# Sheet1.net
KiCad netlist of a schematic drawn in Altium Designer
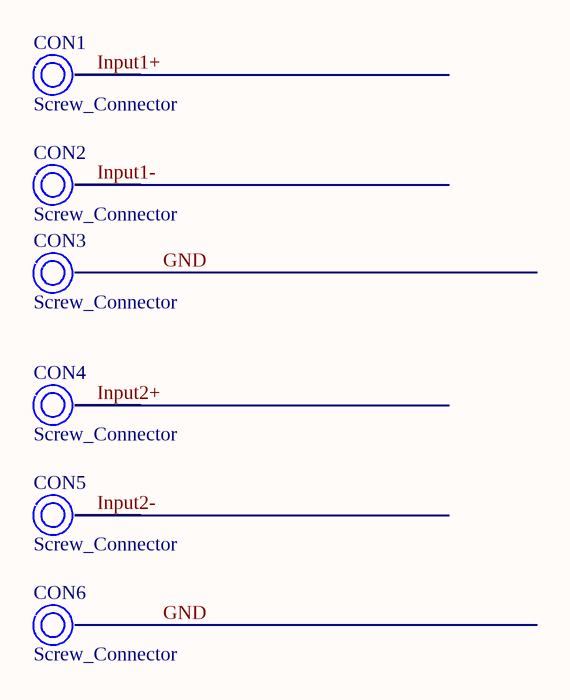
[diagram p0: Sheet1.SchDoc]

(export (version "E")
  (design (tool "Eeschema 10.0.6"))
  (components
    (comp (ref "CON1")
      (value "Screw_Connector")
      (footprint "Screw6x6")
      (libsource (lib "PCB_Project") (part "Screw_Connector"))
    )
    (comp (ref "CON2")
      (value "Screw_Connector")
      (footprint "Screw6x6")
      (libsource (lib "PCB_Project") (part "Screw_Connector"))
    )
    (comp (ref "CON3")
      (value "Screw_Connector")
      (footprint "Screw6x6")
      (libsource (lib "PCB_Project") (part "Screw_Connector"))
    )
    (comp (ref "CON4")
      (value "Screw_Connector")
      (footprint "Screw6x6")
      (libsource (lib "PCB_Project") (part "Screw_Connector"))
    )
    (comp (ref "CON5")
      (value "Screw_Connector")
      (footprint "Screw6x6")
      (libsource (lib "PCB_Project") (part "Screw_Connector"))
    )
    (comp (ref "CON6")
      (value "Screw_Connector")
      (footprint "Screw6x6")
      (libsource (lib "PCB_Project") (part "Screw_Connector"))
    )
  )
  (nets
    (net (code "1") (name "/GND") (class "Default")
      (node (ref "CON3") (pin "1") (pinfunction "1_1") (pintype "passive"))
      (node (ref "CON6") (pin "1") (pinfunction "1_1") (pintype "passive"))
    )
    (net (code "2") (name "/Input1+") (class "Default")
      (node (ref "CON1") (pin "1") (pinfunction "1_1") (pintype "passive"))
    )
    (net (code "3") (name "/Input1-") (class "Default")
      (node (ref "CON2") (pin "1") (pinfunction "1_1") (pintype "passive"))
    )
    (net (code "4") (name "/Input2+") (class "Default")
      (node (ref "CON4") (pin "1") (pinfunction "1_1") (pintype "passive"))
    )
    (net (code "5") (name "/Input2-") (class "Default")
      (node (ref "CON5") (pin "1") (pinfunction "1_1") (pintype "passive"))
    )
  )
)
